# simulation.net
KiCad netlist of a schematic drawn in Altium Designer
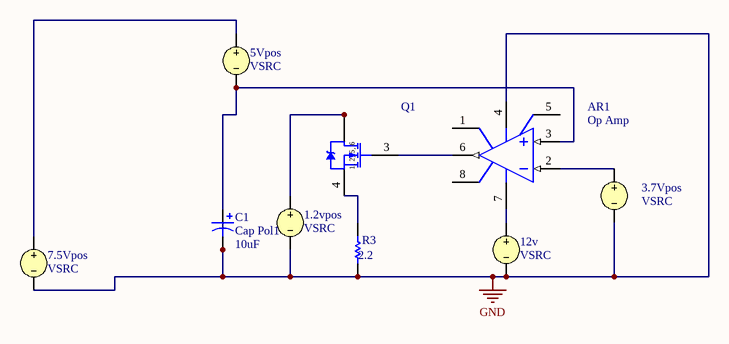
[diagram p0: simulation.SchDoc]

(export (version "E")
  (design (tool "Eeschema 10.0.6"))
  (components
    (comp (ref "1.2vpos")
      (value "VSRC")
      (description "Voltage Source")
      (fields (field (name "PUBLISHER") "Altium Limited"))
      (libsource (lib "Simulation Sources") (part "VSRC"))
    )
    (comp (ref "3.7Vpos")
      (value "VSRC")
      (description "Voltage Source")
      (fields (field (name "PUBLISHER") "Altium Limited"))
      (libsource (lib "Simulation Sources") (part "VSRC"))
    )
    (comp (ref "5Vpos")
      (value "VSRC")
      (description "Voltage Source")
      (fields (field (name "PUBLISHER") "Altium Limited"))
      (libsource (lib "Simulation Sources") (part "VSRC"))
    )
    (comp (ref "7.5Vpos")
      (value "VSRC")
      (description "Voltage Source")
      (fields (field (name "PUBLISHER") "Altium Limited"))
      (libsource (lib "Simulation Sources") (part "VSRC"))
    )
    (comp (ref "12v")
      (value "VSRC")
      (description "Voltage Source")
      (fields (field (name "PUBLISHER") "Altium Limited"))
      (libsource (lib "Simulation Sources") (part "VSRC"))
    )
    (comp (ref "AR1")
      (value "Op Amp")
      (footprint "H-08A")
      (description "FET Operational Amplifier")
      (fields (field (name "PUBLISHER") "Altium Limited"))
      (libsource (lib "Miscellaneous Devices") (part "Op Amp"))
    )
    (comp (ref "C1")
      (value "Cap Pol1")
      (footprint "RB7.6-15")
      (description "Polarized Capacitor (Radial)")
      (fields (field (name "ALTIUM_VALUE") "10uF") (field (name "PUBLISHER") "Altium Limited"))
      (libsource (lib "Miscellaneous Devices") (part "Cap Pol1"))
    )
    (comp (ref "Q1")
      (value "~")
      (footprint "TSOP-6")
      (description "HEXFET Power MOSFET")
      (fields (field (name "PUBLISHER") "Altium Limited"))
      (libsource (lib "*") (part "IRF5801"))
    )
    (comp (ref "R3")
      (value "2.2")
      (footprint "AXIAL-0.4")
      (description "Resistor")
      (fields (field (name "Comment") "resistor") (field (name "PUBLISHER") "Altium Limited"))
      (libsource (lib "agus_lib") (part "RES"))
    )
  )
  (nets
    (net (code "1") (name "GND") (class "Default")
      (node (ref "1.2vpos") (pin "2") (pinfunction "2_2") (pintype "passive"))
      (node (ref "12v") (pin "2") (pinfunction "2_2") (pintype "passive"))
      (node (ref "3.7Vpos") (pin "2") (pinfunction "2_2") (pintype "passive"))
      (node (ref "7.5Vpos") (pin "2") (pinfunction "2_2") (pintype "passive"))
      (node (ref "AR1") (pin "4") (pinfunction "V-_4") (pintype "power_in"))
      (node (ref "C1") (pin "2") (pinfunction "2_2") (pintype "passive"))
      (node (ref "R3") (pin "1") (pinfunction "1_1") (pintype "passive"))
    )
    (net (code "2") (name "Net-(1.2vpos-Pad1)") (class "Default")
      (node (ref "1.2vpos") (pin "1") (pinfunction "1_1") (pintype "passive"))
      (node (ref "Q1") (pin "1") (pinfunction "D_1") (pintype "passive"))
      (node (ref "Q1") (pin "2") (pinfunction "D_2") (pintype "passive"))
      (node (ref "Q1") (pin "5") (pinfunction "D_5") (pintype "passive"))
      (node (ref "Q1") (pin "6") (pinfunction "D_6") (pintype "passive"))
    )
    (net (code "3") (name "Net-(5Vpos-Pad1)") (class "Default")
      (node (ref "5Vpos") (pin "1") (pinfunction "1_1") (pintype "passive"))
      (node (ref "7.5Vpos") (pin "1") (pinfunction "1_1") (pintype "passive"))
    )
    (net (code "4") (name "Net-(AR1-IN+)") (class "Default")
      (node (ref "5Vpos") (pin "2") (pinfunction "2_2") (pintype "passive"))
      (node (ref "AR1") (pin "3") (pinfunction "IN+_3") (pintype "input"))
      (node (ref "C1") (pin "1") (pinfunction "1_1") (pintype "passive"))
    )
    (net (code "5") (name "Net-(AR1-IN-)") (class "Default")
      (node (ref "3.7Vpos") (pin "1") (pinfunction "1_1") (pintype "passive"))
      (node (ref "AR1") (pin "2") (pinfunction "IN-_2") (pintype "input"))
    )
    (net (code "6") (name "Net-(AR1-OUT)") (class "Default")
      (node (ref "AR1") (pin "6") (pinfunction "OUT_6") (pintype "output"))
      (node (ref "Q1") (pin "3") (pinfunction "G_3") (pintype "passive"))
    )
    (net (code "7") (name "Net-(AR1-V+)") (class "Default")
      (node (ref "12v") (pin "1") (pinfunction "1_1") (pintype "passive"))
      (node (ref "AR1") (pin "7") (pinfunction "V+_7") (pintype "power_in"))
    )
    (net (code "8") (name "Net-(Q1-S)") (class "Default")
      (node (ref "Q1") (pin "4") (pinfunction "S_4") (pintype "passive"))
      (node (ref "R3") (pin "2") (pinfunction "2_2") (pintype "passive"))
    )
    (net (code "9") (name "unconnected-(AR1-OS_NUL-Pad1)") (class "Default")
      (node (ref "AR1") (pin "1") (pinfunction "OS_NUL_1") (pintype "passive"))
    )
    (net (code "10") (name "unconnected-(AR1-OS_NUL-Pad5)") (class "Default")
      (node (ref "AR1") (pin "5") (pinfunction "OS_NUL_5") (pintype "passive"))
    )
    (net (code "11") (name "unconnected-(AR1-TAB-Pad8)") (class "Default")
      (node (ref "AR1") (pin "8") (pinfunction "TAB_8") (pintype "passive"))
    )
  )
)
